# breakoutboard.net
KiCad netlist of a schematic drawn in EAGLE
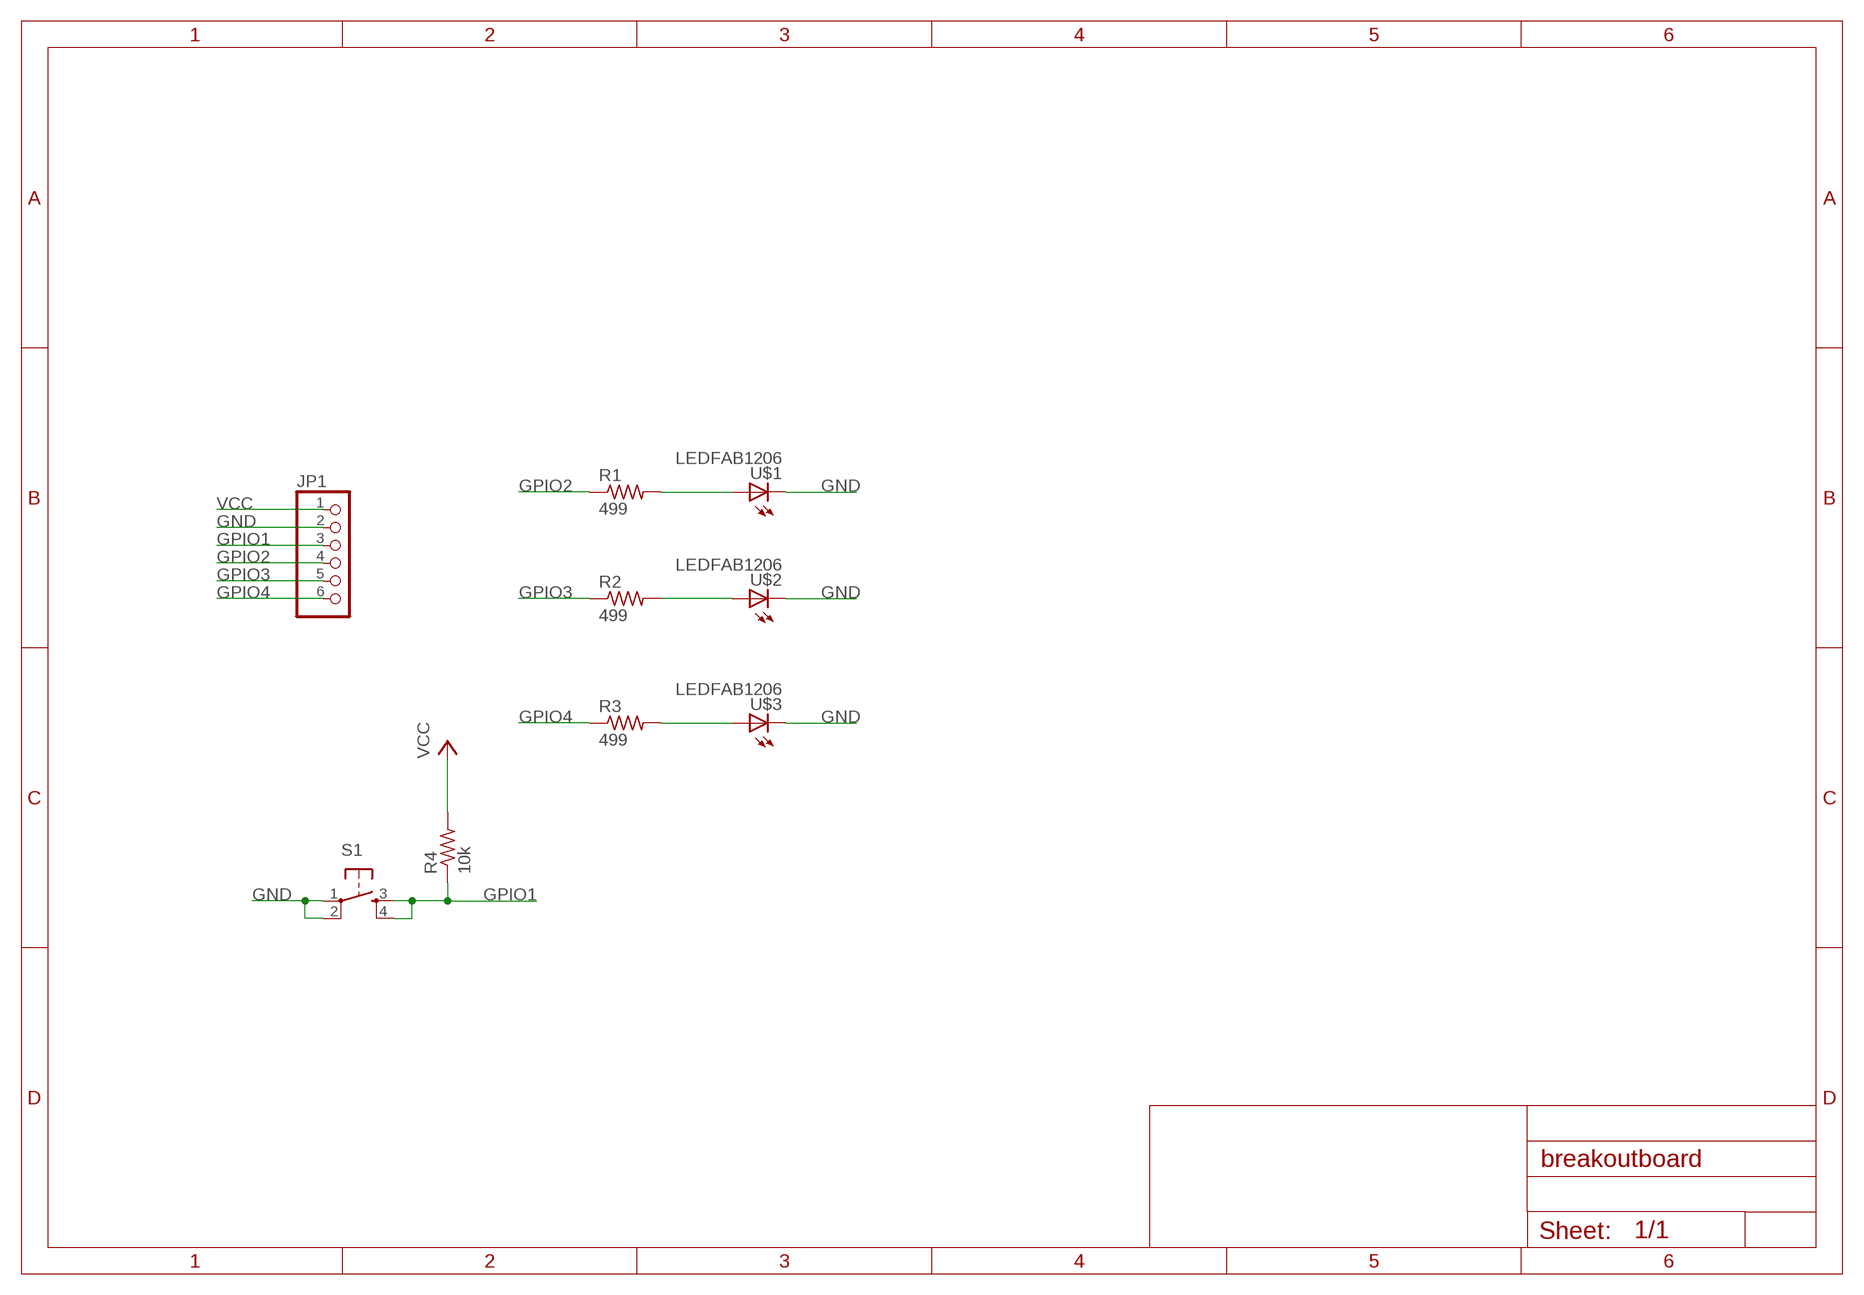
[diagram p0: schematic, sheet 1]

(export (version "E")
  (design (tool "Eeschema 10.0.6"))
  (components
    (comp (ref "JP1")
      (value "PINHD-1X6")
      (footprint "eagle-import:1X06")
      (libsource (lib "eagle-import") (part "PINHD-1X6"))
    )
    (comp (ref "R1")
      (value "499")
      (footprint "eagle-import:R1206FAB")
      (libsource (lib "eagle-import") (part "R1206FAB"))
    )
    (comp (ref "R2")
      (value "499")
      (footprint "eagle-import:R1206FAB")
      (libsource (lib "eagle-import") (part "R1206FAB"))
    )
    (comp (ref "R3")
      (value "499")
      (footprint "eagle-import:R1206FAB")
      (libsource (lib "eagle-import") (part "R1206FAB"))
    )
    (comp (ref "R4")
      (value "10k")
      (footprint "eagle-import:R1206FAB")
      (libsource (lib "eagle-import") (part "R1206FAB"))
    )
    (comp (ref "S1")
      (value "SW_SWITCH_TACTILE_6MM6MM_SWITCH")
      (footprint "eagle-import:6MM_SWITCH")
      (libsource (lib "eagle-import") (part "SW_SWITCH_TACTILE_6MM6MM_SWITCH"))
    )
    (comp (ref "U$1")
      (value "LEDFAB1206")
      (footprint "eagle-import:LED1206FAB")
      (libsource (lib "eagle-import") (part "LEDFAB1206"))
    )
    (comp (ref "U$2")
      (value "LEDFAB1206")
      (footprint "eagle-import:LED1206FAB")
      (libsource (lib "eagle-import") (part "LEDFAB1206"))
    )
    (comp (ref "U$3")
      (value "LEDFAB1206")
      (footprint "eagle-import:LED1206FAB")
      (libsource (lib "eagle-import") (part "LEDFAB1206"))
    )
  )
  (nets
    (net (code "1") (name "/GND") (class "Default")
      (node (ref "JP1") (pin "2") (pinfunction "2_2") (pintype "passive"))
      (node (ref "S1") (pin "1") (pinfunction "P_1") (pintype "passive"))
      (node (ref "S1") (pin "2") (pinfunction "P1_2") (pintype "passive"))
      (node (ref "U$1") (pin "2") (pinfunction "C_2") (pintype "passive"))
      (node (ref "U$2") (pin "2") (pinfunction "C_2") (pintype "passive"))
      (node (ref "U$3") (pin "2") (pinfunction "C_2") (pintype "passive"))
    )
    (net (code "2") (name "/GPIO1") (class "Default")
      (node (ref "JP1") (pin "3") (pinfunction "3_3") (pintype "passive"))
      (node (ref "R4") (pin "1") (pinfunction "1_1") (pintype "passive"))
      (node (ref "S1") (pin "3") (pinfunction "S_3") (pintype "passive"))
      (node (ref "S1") (pin "4") (pinfunction "S1_4") (pintype "passive"))
    )
    (net (code "3") (name "/GPIO2") (class "Default")
      (node (ref "JP1") (pin "4") (pinfunction "4_4") (pintype "passive"))
      (node (ref "R1") (pin "1") (pinfunction "1_1") (pintype "passive"))
    )
    (net (code "4") (name "/GPIO3") (class "Default")
      (node (ref "JP1") (pin "5") (pinfunction "5_5") (pintype "passive"))
      (node (ref "R2") (pin "1") (pinfunction "1_1") (pintype "passive"))
    )
    (net (code "5") (name "/GPIO4") (class "Default")
      (node (ref "JP1") (pin "6") (pinfunction "6_6") (pintype "passive"))
      (node (ref "R3") (pin "1") (pinfunction "1_1") (pintype "passive"))
    )
    (net (code "6") (name "Net-(U$1-A)") (class "Default")
      (node (ref "R1") (pin "2") (pinfunction "2_2") (pintype "passive"))
      (node (ref "U$1") (pin "1") (pinfunction "A_1") (pintype "passive"))
    )
    (net (code "7") (name "Net-(U$2-A)") (class "Default")
      (node (ref "R2") (pin "2") (pinfunction "2_2") (pintype "passive"))
      (node (ref "U$2") (pin "1") (pinfunction "A_1") (pintype "passive"))
    )
    (net (code "8") (name "Net-(U$3-A)") (class "Default")
      (node (ref "R3") (pin "2") (pinfunction "2_2") (pintype "passive"))
      (node (ref "U$3") (pin "1") (pinfunction "A_1") (pintype "passive"))
    )
    (net (code "9") (name "VCC") (class "Default")
      (node (ref "JP1") (pin "1") (pinfunction "1_1") (pintype "passive"))
      (node (ref "R4") (pin "2") (pinfunction "2_2") (pintype "passive"))
    )
  )
)
